# Display.net
KiCad netlist of a schematic drawn in EAGLE
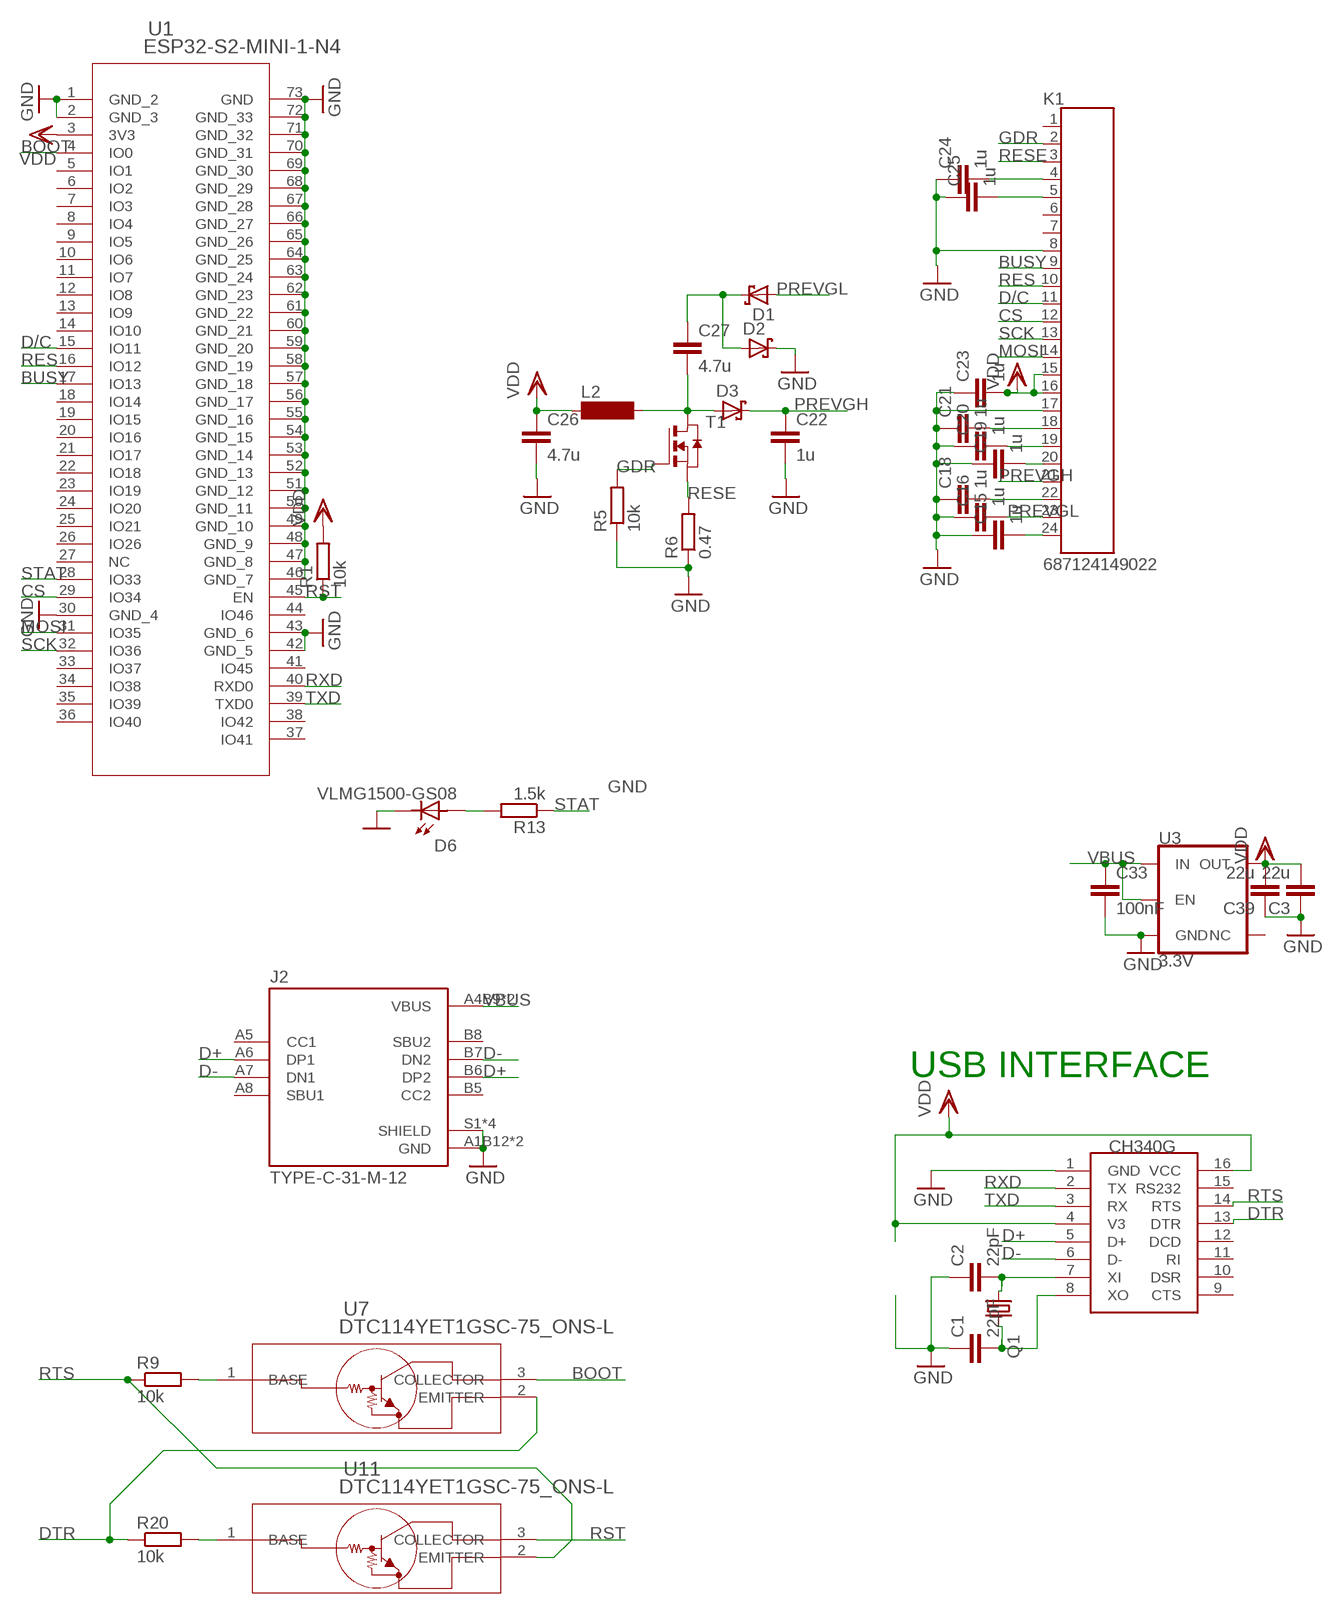
[diagram p0: schematic, sheet 1]

(export (version "E")
  (design (tool "Eeschema 10.0.6"))
  (components
    (comp (ref "C1")
      (value "22pF")
      (footprint "eagle-import:C0402")
      (libsource (lib "eagle-import") (part "CC0402"))
    )
    (comp (ref "C2")
      (value "22pF")
      (footprint "eagle-import:C0402")
      (libsource (lib "eagle-import") (part "CC0402"))
    )
    (comp (ref "C3")
      (value "22u")
      (footprint "eagle-import:C0603R")
      (libsource (lib "eagle-import") (part "CC0603R"))
    )
    (comp (ref "C15")
      (value "1u")
      (footprint "eagle-import:C0402")
      (libsource (lib "eagle-import") (part "CC0402"))
    )
    (comp (ref "C16")
      (value "1u")
      (footprint "eagle-import:C0402")
      (libsource (lib "eagle-import") (part "CC0402"))
    )
    (comp (ref "C18")
      (value "1u")
      (footprint "eagle-import:C0402")
      (libsource (lib "eagle-import") (part "CC0402"))
    )
    (comp (ref "C19")
      (value "1u")
      (footprint "eagle-import:C0402")
      (libsource (lib "eagle-import") (part "CC0402"))
    )
    (comp (ref "C20")
      (value "1u")
      (footprint "eagle-import:C0402")
      (libsource (lib "eagle-import") (part "CC0402"))
    )
    (comp (ref "C21")
      (value "1u")
      (footprint "eagle-import:C0402")
      (libsource (lib "eagle-import") (part "CC0402"))
    )
    (comp (ref "C22")
      (value "1u")
      (footprint "eagle-import:C0402")
      (libsource (lib "eagle-import") (part "CC0402"))
    )
    (comp (ref "C23")
      (value "1u")
      (footprint "eagle-import:C0402")
      (libsource (lib "eagle-import") (part "CC0402"))
    )
    (comp (ref "C24")
      (value "1u")
      (footprint "eagle-import:C0402")
      (libsource (lib "eagle-import") (part "CC0402"))
    )
    (comp (ref "C25")
      (value "1u")
      (footprint "eagle-import:C0402")
      (libsource (lib "eagle-import") (part "CC0402"))
    )
    (comp (ref "C26")
      (value "4.7u")
      (footprint "eagle-import:C0402")
      (libsource (lib "eagle-import") (part "CC0402"))
    )
    (comp (ref "C27")
      (value "4.7u")
      (footprint "eagle-import:C0402")
      (libsource (lib "eagle-import") (part "CC0402"))
    )
    (comp (ref "C33")
      (value "100nF")
      (footprint "eagle-import:C0402")
      (libsource (lib "eagle-import") (part "CC0402"))
    )
    (comp (ref "C39")
      (value "22u")
      (footprint "eagle-import:C0603R")
      (libsource (lib "eagle-import") (part "CC0603R"))
    )
    (comp (ref "D1")
      (value "1PS79SB30,115")
      (footprint "eagle-import:SOD523")
      (fields (field (name "MF") "Nexperia"))
      (libsource (lib "eagle-import") (part "1PS79SB30,115"))
    )
    (comp (ref "D2")
      (value "1PS79SB30,115")
      (footprint "eagle-import:SOD523")
      (fields (field (name "MF") "Nexperia"))
      (libsource (lib "eagle-import") (part "1PS79SB30,115"))
    )
    (comp (ref "D3")
      (value "1PS79SB30,115")
      (footprint "eagle-import:SOD523")
      (fields (field (name "MF") "Nexperia"))
      (libsource (lib "eagle-import") (part "1PS79SB30,115"))
    )
    (comp (ref "D6")
      (value "VLMG1500-GS08")
      (footprint "eagle-import:LEDC1005X35N")
      (fields (field (name "MF") "Vishay"))
      (libsource (lib "eagle-import") (part "VLMG1500-GS08"))
    )
    (comp (ref "J2")
      (value "TYPE-C-31-M-12")
      (footprint "eagle-import:HRO_TYPE-C-31-M-12")
      (fields (field (name "MF") "HRO Electronics Co., Ltd."))
      (libsource (lib "eagle-import") (part "TYPE-C-31-M-12"))
    )
    (comp (ref "K1")
      (value "687124149022")
      (footprint "eagle-import:687124149022")
      (fields (field (name "MF") "Wurth Electronics"))
      (libsource (lib "eagle-import") (part "687124149022"))
    )
    (comp (ref "L2")
      (value "SM-NE29")
      (footprint "eagle-import:SM-NE29")
      (libsource (lib "eagle-import") (part "SM-NE29"))
    )
    (comp (ref "Q1")
      (value "KX-7")
      (footprint "eagle-import:3.2X2.5_KX-7")
      (libsource (lib "eagle-import") (part "KX-7"))
    )
    (comp (ref "R1")
      (value "10k")
      (footprint "eagle-import:R0402")
      (libsource (lib "eagle-import") (part "RR0402"))
    )
    (comp (ref "R5")
      (value "10k")
      (footprint "eagle-import:R0402")
      (libsource (lib "eagle-import") (part "RR0402"))
    )
    (comp (ref "R6")
      (value "0.47")
      (footprint "eagle-import:R0402")
      (libsource (lib "eagle-import") (part "RR0402"))
    )
    (comp (ref "R9")
      (value "10k")
      (footprint "eagle-import:R0402")
      (libsource (lib "eagle-import") (part "RR0402"))
    )
    (comp (ref "R13")
      (value "1.5k")
      (footprint "eagle-import:R0402")
      (libsource (lib "eagle-import") (part "RR0402"))
    )
    (comp (ref "R20")
      (value "10k")
      (footprint "eagle-import:R0402")
      (libsource (lib "eagle-import") (part "RR0402"))
    )
    (comp (ref "T1")
      (value "NMOSSOT23")
      (footprint "eagle-import:SOT-23")
      (libsource (lib "eagle-import") (part "NMOSSOT23"))
    )
    (comp (ref "U1")
      (value "ESP32-S2-MINI-1-N4")
      (footprint "eagle-import:ESP32-S2-MINI-1-N4_EXP")
      (fields (field (name "COPYRIGHT") "Copyright (C) 2022 Ultra Librarian. All rights reserved."))
      (libsource (lib "eagle-import") (part "ESP32-S2-MINI-1-N4"))
    )
    (comp (ref "U3")
      (value "3.3V")
      (footprint "eagle-import:SOT23-5")
      (libsource (lib "eagle-import") (part "V_REG_AP2112K-3.3V"))
    )
    (comp (ref "U5")
      (value "H")
      (footprint "eagle-import:SOIC16")
      (libsource (lib "eagle-import") (part "CH340G"))
    )
    (comp (ref "U7")
      (value "DTC114YET1GSC-75_ONS-L")
      (footprint "eagle-import:SC-75_ONS-L")
      (fields
        (field (name "MANUFACTURER_PART_NUMBER") "DTC114YET1G")
        (field (name "COPYRIGHT") "Copyright (C) 2018 Accelerated Designs. All rights reserved")
      )
      (libsource (lib "eagle-import") (part "DTC114YET1GSC-75_ONS-L"))
    )
    (comp (ref "U11")
      (value "DTC114YET1GSC-75_ONS-L")
      (footprint "eagle-import:SC-75_ONS-L")
      (fields
        (field (name "MANUFACTURER_PART_NUMBER") "DTC114YET1G")
        (field (name "COPYRIGHT") "Copyright (C) 2018 Accelerated Designs. All rights reserved")
      )
      (libsource (lib "eagle-import") (part "DTC114YET1GSC-75_ONS-L"))
    )
  )
  (nets
    (net (code "1") (name "/BOOT") (class "Default")
      (node (ref "U1") (pin "4") (pinfunction "IO0_4") (pintype "bidirectional"))
      (node (ref "U7") (pin "3") (pinfunction "COLLECTOR_3") (pintype "output"))
    )
    (net (code "2") (name "/BUSY") (class "Default")
      (node (ref "K1") (pin "9") (pinfunction "9_9") (pintype "passive"))
      (node (ref "U1") (pin "17") (pinfunction "IO13_17") (pintype "bidirectional"))
    )
    (net (code "3") (name "/CS") (class "Default")
      (node (ref "K1") (pin "12") (pinfunction "12_12") (pintype "passive"))
      (node (ref "U1") (pin "29") (pinfunction "IO34_29") (pintype "bidirectional"))
    )
    (net (code "4") (name "/D+") (class "Default")
      (node (ref "J2") (pin "A6") (pinfunction "DP1_A6") (pintype "bidirectional"))
      (node (ref "J2") (pin "B6") (pinfunction "DP2_B6") (pintype "bidirectional"))
      (node (ref "U5") (pin "5") (pinfunction "D+_5") (pintype "bidirectional"))
    )
    (net (code "5") (name "/D-") (class "Default")
      (node (ref "J2") (pin "A7") (pinfunction "DN1_A7") (pintype "bidirectional"))
      (node (ref "J2") (pin "B7") (pinfunction "DN2_B7") (pintype "bidirectional"))
      (node (ref "U5") (pin "6") (pinfunction "D-_6") (pintype "bidirectional"))
    )
    (net (code "6") (name "/DTR") (class "Default")
      (node (ref "R20") (pin "1") (pinfunction "1_1") (pintype "passive"))
      (node (ref "U5") (pin "13") (pinfunction "DTR_13") (pintype "bidirectional"))
      (node (ref "U7") (pin "2") (pinfunction "EMITTER_2") (pintype "passive"))
    )
    (net (code "7") (name "/D{slash}C") (class "Default")
      (node (ref "K1") (pin "11") (pinfunction "11_11") (pintype "passive"))
      (node (ref "U1") (pin "15") (pinfunction "IO11_15") (pintype "bidirectional"))
    )
    (net (code "8") (name "/GDR") (class "Default")
      (node (ref "K1") (pin "2") (pinfunction "2_2") (pintype "passive"))
      (node (ref "R5") (pin "2") (pinfunction "2_2") (pintype "passive"))
      (node (ref "T1") (pin "3") (pinfunction "G_3") (pintype "passive"))
    )
    (net (code "9") (name "/MOSI") (class "Default")
      (node (ref "K1") (pin "14") (pinfunction "14_14") (pintype "passive"))
      (node (ref "U1") (pin "31") (pinfunction "IO35_31") (pintype "bidirectional"))
    )
    (net (code "10") (name "/PREVGH") (class "Default")
      (node (ref "C22") (pin "1") (pinfunction "1_1") (pintype "passive"))
      (node (ref "D3") (pin "1") (pinfunction "K_1") (pintype "passive"))
      (node (ref "K1") (pin "21") (pinfunction "21_21") (pintype "passive"))
    )
    (net (code "11") (name "/PREVGL") (class "Default")
      (node (ref "C16") (pin "2") (pinfunction "2_2") (pintype "passive"))
      (node (ref "D1") (pin "2") (pinfunction "A_2") (pintype "passive"))
      (node (ref "K1") (pin "23") (pinfunction "23_23") (pintype "passive"))
    )
    (net (code "12") (name "/RES") (class "Default")
      (node (ref "K1") (pin "10") (pinfunction "10_10") (pintype "passive"))
      (node (ref "U1") (pin "16") (pinfunction "IO12_16") (pintype "bidirectional"))
    )
    (net (code "13") (name "/RESE") (class "Default")
      (node (ref "K1") (pin "3") (pinfunction "3_3") (pintype "passive"))
      (node (ref "R6") (pin "2") (pinfunction "2_2") (pintype "passive"))
      (node (ref "T1") (pin "2") (pinfunction "S_2") (pintype "passive"))
    )
    (net (code "14") (name "/RST") (class "Default")
      (node (ref "R1") (pin "1") (pinfunction "1_1") (pintype "passive"))
      (node (ref "U1") (pin "45") (pinfunction "EN_45") (pintype "passive"))
      (node (ref "U11") (pin "3") (pinfunction "COLLECTOR_3") (pintype "output"))
    )
    (net (code "15") (name "/RTS") (class "Default")
      (node (ref "R9") (pin "1") (pinfunction "1_1") (pintype "passive"))
      (node (ref "U11") (pin "2") (pinfunction "EMITTER_2") (pintype "passive"))
      (node (ref "U5") (pin "14") (pinfunction "RTS_14") (pintype "bidirectional"))
    )
    (net (code "16") (name "/RXD") (class "Default")
      (node (ref "U1") (pin "40") (pinfunction "RXD0_40") (pintype "bidirectional"))
      (node (ref "U5") (pin "2") (pinfunction "TX_2") (pintype "bidirectional"))
    )
    (net (code "17") (name "/SCK") (class "Default")
      (node (ref "K1") (pin "13") (pinfunction "13_13") (pintype "passive"))
      (node (ref "U1") (pin "32") (pinfunction "IO36_32") (pintype "bidirectional"))
    )
    (net (code "18") (name "/STAT") (class "Default")
      (node (ref "R13") (pin "1") (pinfunction "1_1") (pintype "passive"))
      (node (ref "U1") (pin "28") (pinfunction "IO33_28") (pintype "bidirectional"))
    )
    (net (code "19") (name "/TXD") (class "Default")
      (node (ref "U1") (pin "39") (pinfunction "TXD0_39") (pintype "bidirectional"))
      (node (ref "U5") (pin "3") (pinfunction "RX_3") (pintype "bidirectional"))
    )
    (net (code "20") (name "/VBUS") (class "Default")
      (node (ref "C33") (pin "1") (pinfunction "1_1") (pintype "passive"))
      (node (ref "J2") (pin "A4B9") (pinfunction "VBUS_A4B9") (pintype "power_in"))
      (node (ref "J2") (pin "B4A9") (pinfunction "VBUS_B4A9") (pintype "power_in"))
      (node (ref "U3") (pin "1") (pinfunction "IN_1") (pintype "input"))
      (node (ref "U3") (pin "3") (pinfunction "EN_3") (pintype "input"))
    )
    (net (code "21") (name "GND") (class "Default")
      (node (ref "C1") (pin "1") (pinfunction "1_1") (pintype "passive"))
      (node (ref "C15") (pin "1") (pinfunction "1_1") (pintype "passive"))
      (node (ref "C16") (pin "1") (pinfunction "1_1") (pintype "passive"))
      (node (ref "C18") (pin "1") (pinfunction "1_1") (pintype "passive"))
      (node (ref "C19") (pin "1") (pinfunction "1_1") (pintype "passive"))
      (node (ref "C2") (pin "1") (pinfunction "1_1") (pintype "passive"))
      (node (ref "C20") (pin "1") (pinfunction "1_1") (pintype "passive"))
      (node (ref "C21") (pin "1") (pinfunction "1_1") (pintype "passive"))
      (node (ref "C22") (pin "2") (pinfunction "2_2") (pintype "passive"))
      (node (ref "C23") (pin "1") (pinfunction "1_1") (pintype "passive"))
      (node (ref "C24") (pin "1") (pinfunction "1_1") (pintype "passive"))
      (node (ref "C25") (pin "1") (pinfunction "1_1") (pintype "passive"))
      (node (ref "C26") (pin "2") (pinfunction "2_2") (pintype "passive"))
      (node (ref "C3") (pin "1") (pinfunction "1_1") (pintype "passive"))
      (node (ref "C33") (pin "2") (pinfunction "2_2") (pintype "passive"))
      (node (ref "C39") (pin "1") (pinfunction "1_1") (pintype "passive"))
      (node (ref "D2") (pin "1") (pinfunction "K_1") (pintype "passive"))
      (node (ref "D6") (pin "2") (pinfunction "2_2") (pintype "passive"))
      (node (ref "J2") (pin "A1B12") (pinfunction "GND_A1B12") (pintype "power_in"))
      (node (ref "J2") (pin "B1A12") (pinfunction "GND_B1A12") (pintype "power_in"))
      (node (ref "J2") (pin "S1") (pinfunction "SHIELD_S1") (pintype "passive"))
      (node (ref "J2") (pin "S2") (pinfunction "SHIELD_S2") (pintype "passive"))
      (node (ref "J2") (pin "S3") (pinfunction "SHIELD_S3") (pintype "passive"))
      (node (ref "J2") (pin "S4") (pinfunction "SHIELD_S4") (pintype "passive"))
      (node (ref "K1") (pin "17") (pinfunction "17_17") (pintype "passive"))
      (node (ref "K1") (pin "8") (pinfunction "8_8") (pintype "passive"))
      (node (ref "R5") (pin "1") (pinfunction "1_1") (pintype "passive"))
      (node (ref "R6") (pin "1") (pinfunction "1_1") (pintype "passive"))
      (node (ref "U1") (pin "1") (pinfunction "GND_2_1") (pintype "passive"))
      (node (ref "U1") (pin "2") (pinfunction "GND_3_2") (pintype "passive"))
      (node (ref "U1") (pin "30") (pinfunction "GND_4_30") (pintype "passive"))
      (node (ref "U1") (pin "42") (pinfunction "GND_5_42") (pintype "passive"))
      (node (ref "U1") (pin "43") (pinfunction "GND_6_43") (pintype "passive"))
      (node (ref "U1") (pin "46") (pinfunction "GND_7_46") (pintype "passive"))
      (node (ref "U1") (pin "47") (pinfunction "GND_8_47") (pintype "passive"))
      (node (ref "U1") (pin "48") (pinfunction "GND_9_48") (pintype "passive"))
      (node (ref "U1") (pin "49") (pinfunction "GND_10_49") (pintype "passive"))
      (node (ref "U1") (pin "50") (pinfunction "GND_11_50") (pintype "passive"))
      (node (ref "U1") (pin "51") (pinfunction "GND_12_51") (pintype "passive"))
      (node (ref "U1") (pin "52") (pinfunction "GND_13_52") (pintype "passive"))
      (node (ref "U1") (pin "53") (pinfunction "GND_14_53") (pintype "passive"))
      (node (ref "U1") (pin "54") (pinfunction "GND_15_54") (pintype "passive"))
      (node (ref "U1") (pin "55") (pinfunction "GND_16_55") (pintype "passive"))
      (node (ref "U1") (pin "56") (pinfunction "GND_17_56") (pintype "passive"))
      (node (ref "U1") (pin "57") (pinfunction "GND_18_57") (pintype "passive"))
      (node (ref "U1") (pin "58") (pinfunction "GND_19_58") (pintype "passive"))
      (node (ref "U1") (pin "59") (pinfunction "GND_20_59") (pintype "passive"))
      (node (ref "U1") (pin "60") (pinfunction "GND_21_60") (pintype "passive"))
      (node (ref "U1") (pin "61") (pinfunction "GND_22_61") (pintype "passive"))
      (node (ref "U1") (pin "62") (pinfunction "GND_23_62") (pintype "passive"))
      (node (ref "U1") (pin "63") (pinfunction "GND_24_63") (pintype "passive"))
      (node (ref "U1") (pin "64") (pinfunction "GND_25_64") (pintype "passive"))
      (node (ref "U1") (pin "65") (pinfunction "GND_26_65") (pintype "passive"))
      (node (ref "U1") (pin "66") (pinfunction "GND_27_66") (pintype "passive"))
      (node (ref "U1") (pin "67") (pinfunction "GND_28_67") (pintype "passive"))
      (node (ref "U1") (pin "68") (pinfunction "GND_29_68") (pintype "passive"))
      (node (ref "U1") (pin "69") (pinfunction "GND_30_69") (pintype "passive"))
      (node (ref "U1") (pin "70") (pinfunction "GND_31_70") (pintype "passive"))
      (node (ref "U1") (pin "71") (pinfunction "GND_32_71") (pintype "passive"))
      (node (ref "U1") (pin "72") (pinfunction "GND_33_72") (pintype "passive"))
      (node (ref "U1") (pin "73") (pinfunction "GND_73") (pintype "passive"))
      (node (ref "U3") (pin "2") (pinfunction "GND_2") (pintype "input"))
      (node (ref "U5") (pin "1") (pinfunction "GND_1") (pintype "bidirectional"))
    )
    (net (code "22") (name "Net-(C15-Pad2)") (class "Default")
      (node (ref "C15") (pin "2") (pinfunction "2_2") (pintype "passive"))
      (node (ref "K1") (pin "24") (pinfunction "24_24") (pintype "passive"))
    )
    (net (code "23") (name "Net-(C18-Pad2)") (class "Default")
      (node (ref "C18") (pin "2") (pinfunction "2_2") (pintype "passive"))
      (node (ref "K1") (pin "22") (pinfunction "22_22") (pintype "passive"))
    )
    (net (code "24") (name "Net-(C19-Pad2)") (class "Default")
      (node (ref "C19") (pin "2") (pinfunction "2_2") (pintype "passive"))
      (node (ref "K1") (pin "20") (pinfunction "20_20") (pintype "passive"))
    )
    (net (code "25") (name "Net-(C20-Pad2)") (class "Default")
      (node (ref "C20") (pin "2") (pinfunction "2_2") (pintype "passive"))
      (node (ref "K1") (pin "19") (pinfunction "19_19") (pintype "passive"))
    )
    (net (code "26") (name "Net-(C21-Pad2)") (class "Default")
      (node (ref "C21") (pin "2") (pinfunction "2_2") (pintype "passive"))
      (node (ref "K1") (pin "18") (pinfunction "18_18") (pintype "passive"))
    )
    (net (code "27") (name "Net-(C24-Pad2)") (class "Default")
      (node (ref "C24") (pin "2") (pinfunction "2_2") (pintype "passive"))
      (node (ref "K1") (pin "4") (pinfunction "4_4") (pintype "passive"))
    )
    (net (code "28") (name "Net-(C25-Pad2)") (class "Default")
      (node (ref "C25") (pin "2") (pinfunction "2_2") (pintype "passive"))
      (node (ref "K1") (pin "5") (pinfunction "5_5") (pintype "passive"))
    )
    (net (code "29") (name "Net-(D1-K)") (class "Default")
      (node (ref "C27") (pin "1") (pinfunction "1_1") (pintype "passive"))
      (node (ref "D1") (pin "1") (pinfunction "K_1") (pintype "passive"))
      (node (ref "D2") (pin "2") (pinfunction "A_2") (pintype "passive"))
    )
    (net (code "30") (name "Net-(D3-A)") (class "Default")
      (node (ref "C27") (pin "2") (pinfunction "2_2") (pintype "passive"))
      (node (ref "D3") (pin "2") (pinfunction "A_2") (pintype "passive"))
      (node (ref "L2") (pin "2") (pinfunction "2_2") (pintype "passive"))
      (node (ref "T1") (pin "1") (pinfunction "D_1") (pintype "passive"))
    )
    (net (code "31") (name "Net-(D6-Pad1)") (class "Default")
      (node (ref "D6") (pin "1") (pinfunction "1_1") (pintype "passive"))
      (node (ref "R13") (pin "2") (pinfunction "2_2") (pintype "passive"))
    )
    (net (code "32") (name "Net-(Q1-2)") (class "Default")
      (node (ref "C1") (pin "2") (pinfunction "2_2") (pintype "passive"))
      (node (ref "Q1") (pin "3") (pinfunction "2_3") (pintype "passive"))
      (node (ref "U5") (pin "8") (pinfunction "XO_8") (pintype "bidirectional"))
    )
    (net (code "33") (name "Net-(U5-XI)") (class "Default")
      (node (ref "C2") (pin "2") (pinfunction "2_2") (pintype "passive"))
      (node (ref "Q1") (pin "1") (pinfunction "1_1") (pintype "passive"))
      (node (ref "U5") (pin "7") (pinfunction "XI_7") (pintype "bidirectional"))
    )
    (net (code "34") (name "Net-(U7-BASE)") (class "Default")
      (node (ref "R9") (pin "2") (pinfunction "2_2") (pintype "passive"))
      (node (ref "U7") (pin "1") (pinfunction "BASE_1") (pintype "input"))
    )
    (net (code "35") (name "Net-(U11-BASE)") (class "Default")
      (node (ref "R20") (pin "2") (pinfunction "2_2") (pintype "passive"))
      (node (ref "U11") (pin "1") (pinfunction "BASE_1") (pintype "input"))
    )
    (net (code "36") (name "VDD") (class "Default")
      (node (ref "C23") (pin "2") (pinfunction "2_2") (pintype "passive"))
      (node (ref "C26") (pin "1") (pinfunction "1_1") (pintype "passive"))
      (node (ref "C3") (pin "2") (pinfunction "2_2") (pintype "passive"))
      (node (ref "C39") (pin "2") (pinfunction "2_2") (pintype "passive"))
      (node (ref "K1") (pin "15") (pinfunction "15_15") (pintype "passive"))
      (node (ref "K1") (pin "16") (pinfunction "16_16") (pintype "passive"))
      (node (ref "L2") (pin "1") (pinfunction "1_1") (pintype "passive"))
      (node (ref "R1") (pin "2") (pinfunction "2_2") (pintype "passive"))
      (node (ref "U1") (pin "3") (pinfunction "3V3_3") (pintype "passive"))
      (node (ref "U3") (pin "5") (pinfunction "OUT_5") (pintype "passive"))
      (node (ref "U5") (pin "16") (pinfunction "VCC_16") (pintype "bidirectional"))
      (node (ref "U5") (pin "4") (pinfunction "V3_4") (pintype "bidirectional"))
    )
    (net (code "37") (name "unconnected-(J2-CC1-PadA5)") (class "Default")
      (node (ref "J2") (pin "A5") (pinfunction "CC1_A5") (pintype "bidirectional"))
    )
    (net (code "38") (name "unconnected-(J2-CC2-PadB5)") (class "Default")
      (node (ref "J2") (pin "B5") (pinfunction "CC2_B5") (pintype "bidirectional"))
    )
    (net (code "39") (name "unconnected-(J2-SBU1-PadA8)") (class "Default")
      (node (ref "J2") (pin "A8") (pinfunction "SBU1_A8") (pintype "bidirectional"))
    )
    (net (code "40") (name "unconnected-(J2-SBU2-PadB8)") (class "Default")
      (node (ref "J2") (pin "B8") (pinfunction "SBU2_B8") (pintype "bidirectional"))
    )
    (net (code "41") (name "unconnected-(K1-Pad1)") (class "Default")
      (node (ref "K1") (pin "1") (pinfunction "1_1") (pintype "passive"))
    )
    (net (code "42") (name "unconnected-(K1-Pad6)") (class "Default")
      (node (ref "K1") (pin "6") (pinfunction "6_6") (pintype "passive"))
    )
    (net (code "43") (name "unconnected-(K1-Pad7)") (class "Default")
      (node (ref "K1") (pin "7") (pinfunction "7_7") (pintype "passive"))
    )
    (net (code "44") (name "unconnected-(U1-IO1-Pad5)") (class "Default")
      (node (ref "U1") (pin "5") (pinfunction "IO1_5") (pintype "bidirectional"))
    )
    (net (code "45") (name "unconnected-(U1-IO2-Pad6)") (class "Default")
      (node (ref "U1") (pin "6") (pinfunction "IO2_6") (pintype "bidirectional"))
    )
    (net (code "46") (name "unconnected-(U1-IO3-Pad7)") (class "Default")
      (node (ref "U1") (pin "7") (pinfunction "IO3_7") (pintype "bidirectional"))
    )
    (net (code "47") (name "unconnected-(U1-IO4-Pad8)") (class "Default")
      (node (ref "U1") (pin "8") (pinfunction "IO4_8") (pintype "bidirectional"))
    )
    (net (code "48") (name "unconnected-(U1-IO5-Pad9)") (class "Default")
      (node (ref "U1") (pin "9") (pinfunction "IO5_9") (pintype "bidirectional"))
    )
    (net (code "49") (name "unconnected-(U1-IO6-Pad10)") (class "Default")
      (node (ref "U1") (pin "10") (pinfunction "IO6_10") (pintype "bidirectional"))
    )
    (net (code "50") (name "unconnected-(U1-IO7-Pad11)") (class "Default")
      (node (ref "U1") (pin "11") (pinfunction "IO7_11") (pintype "bidirectional"))
    )
    (net (code "51") (name "unconnected-(U1-IO8-Pad12)") (class "Default")
      (node (ref "U1") (pin "12") (pinfunction "IO8_12") (pintype "bidirectional"))
    )
    (net (code "52") (name "unconnected-(U1-IO9-Pad13)") (class "Default")
      (node (ref "U1") (pin "13") (pinfunction "IO9_13") (pintype "bidirectional"))
    )
    (net (code "53") (name "unconnected-(U1-IO10-Pad14)") (class "Default")
      (node (ref "U1") (pin "14") (pinfunction "IO10_14") (pintype "bidirectional"))
    )
    (net (code "54") (name "unconnected-(U1-IO14-Pad18)") (class "Default")
      (node (ref "U1") (pin "18") (pinfunction "IO14_18") (pintype "bidirectional"))
    )
    (net (code "55") (name "unconnected-(U1-IO15-Pad19)") (class "Default")
      (node (ref "U1") (pin "19") (pinfunction "IO15_19") (pintype "bidirectional"))
    )
    (net (code "56") (name "unconnected-(U1-IO16-Pad20)") (class "Default")
      (node (ref "U1") (pin "20") (pinfunction "IO16_20") (pintype "bidirectional"))
    )
    (net (code "57") (name "unconnected-(U1-IO17-Pad21)") (class "Default")
      (node (ref "U1") (pin "21") (pinfunction "IO17_21") (pintype "bidirectional"))
    )
    (net (code "58") (name "unconnected-(U1-IO18-Pad22)") (class "Default")
      (node (ref "U1") (pin "22") (pinfunction "IO18_22") (pintype "bidirectional"))
    )
    (net (code "59") (name "unconnected-(U1-IO19-Pad23)") (class "Default")
      (node (ref "U1") (pin "23") (pinfunction "IO19_23") (pintype "bidirectional"))
    )
    (net (code "60") (name "unconnected-(U1-IO20-Pad24)") (class "Default")
      (node (ref "U1") (pin "24") (pinfunction "IO20_24") (pintype "bidirectional"))
    )
    (net (code "61") (name "unconnected-(U1-IO21-Pad25)") (class "Default")
      (node (ref "U1") (pin "25") (pinfunction "IO21_25") (pintype "bidirectional"))
    )
    (net (code "62") (name "unconnected-(U1-IO26-Pad26)") (class "Default")
      (node (ref "U1") (pin "26") (pinfunction "IO26_26") (pintype "bidirectional"))
    )
    (net (code "63") (name "unconnected-(U1-IO37-Pad33)") (class "Default")
      (node (ref "U1") (pin "33") (pinfunction "IO37_33") (pintype "bidirectional"))
    )
    (net (code "64") (name "unconnected-(U1-IO38-Pad34)") (class "Default")
      (node (ref "U1") (pin "34") (pinfunction "IO38_34") (pintype "bidirectional"))
    )
    (net (code "65") (name "unconnected-(U1-IO39-Pad35)") (class "Default")
      (node (ref "U1") (pin "35") (pinfunction "IO39_35") (pintype "bidirectional"))
    )
    (net (code "66") (name "unconnected-(U1-IO40-Pad36)") (class "Default")
      (node (ref "U1") (pin "36") (pinfunction "IO40_36") (pintype "bidirectional"))
    )
    (net (code "67") (name "unconnected-(U1-IO41-Pad37)") (class "Default")
      (node (ref "U1") (pin "37") (pinfunction "IO41_37") (pintype "bidirectional"))
    )
    (net (code "68") (name "unconnected-(U1-IO42-Pad38)") (class "Default")
      (node (ref "U1") (pin "38") (pinfunction "IO42_38") (pintype "bidirectional"))
    )
    (net (code "69") (name "unconnected-(U1-IO45-Pad41)") (class "Default")
      (node (ref "U1") (pin "41") (pinfunction "IO45_41") (pintype "bidirectional"))
    )
    (net (code "70") (name "unconnected-(U1-IO46-Pad44)") (class "Default")
      (node (ref "U1") (pin "44") (pinfunction "IO46_44") (pintype "bidirectional"))
    )
    (net (code "71") (name "unconnected-(U1-NC-Pad27)") (class "Default")
      (node (ref "U1") (pin "27") (pinfunction "NC_27") (pintype "no_connect"))
    )
    (net (code "72") (name "unconnected-(U3-NC-Pad4)") (class "Default")
      (node (ref "U3") (pin "4") (pinfunction "NC_4") (pintype "no_connect"))
    )
    (net (code "73") (name "unconnected-(U5-CTS-Pad9)") (class "Default")
      (node (ref "U5") (pin "9") (pinfunction "CTS_9") (pintype "bidirectional"))
    )
    (net (code "74") (name "unconnected-(U5-DCD-Pad12)") (class "Default")
      (node (ref "U5") (pin "12") (pinfunction "DCD_12") (pintype "bidirectional"))
    )
    (net (code "75") (name "unconnected-(U5-DSR-Pad10)") (class "Default")
      (node (ref "U5") (pin "10") (pinfunction "DSR_10") (pintype "bidirectional"))
    )
    (net (code "76") (name "unconnected-(U5-RI-Pad11)") (class "Default")
      (node (ref "U5") (pin "11") (pinfunction "RI_11") (pintype "bidirectional"))
    )
    (net (code "77") (name "unconnected-(U5-RS232-Pad15)") (class "Default")
      (node (ref "U5") (pin "15") (pinfunction "RS232_15") (pintype "bidirectional"))
    )
  )
)
